# schematic.net
KiCad netlist of a schematic drawn in Altium Designer
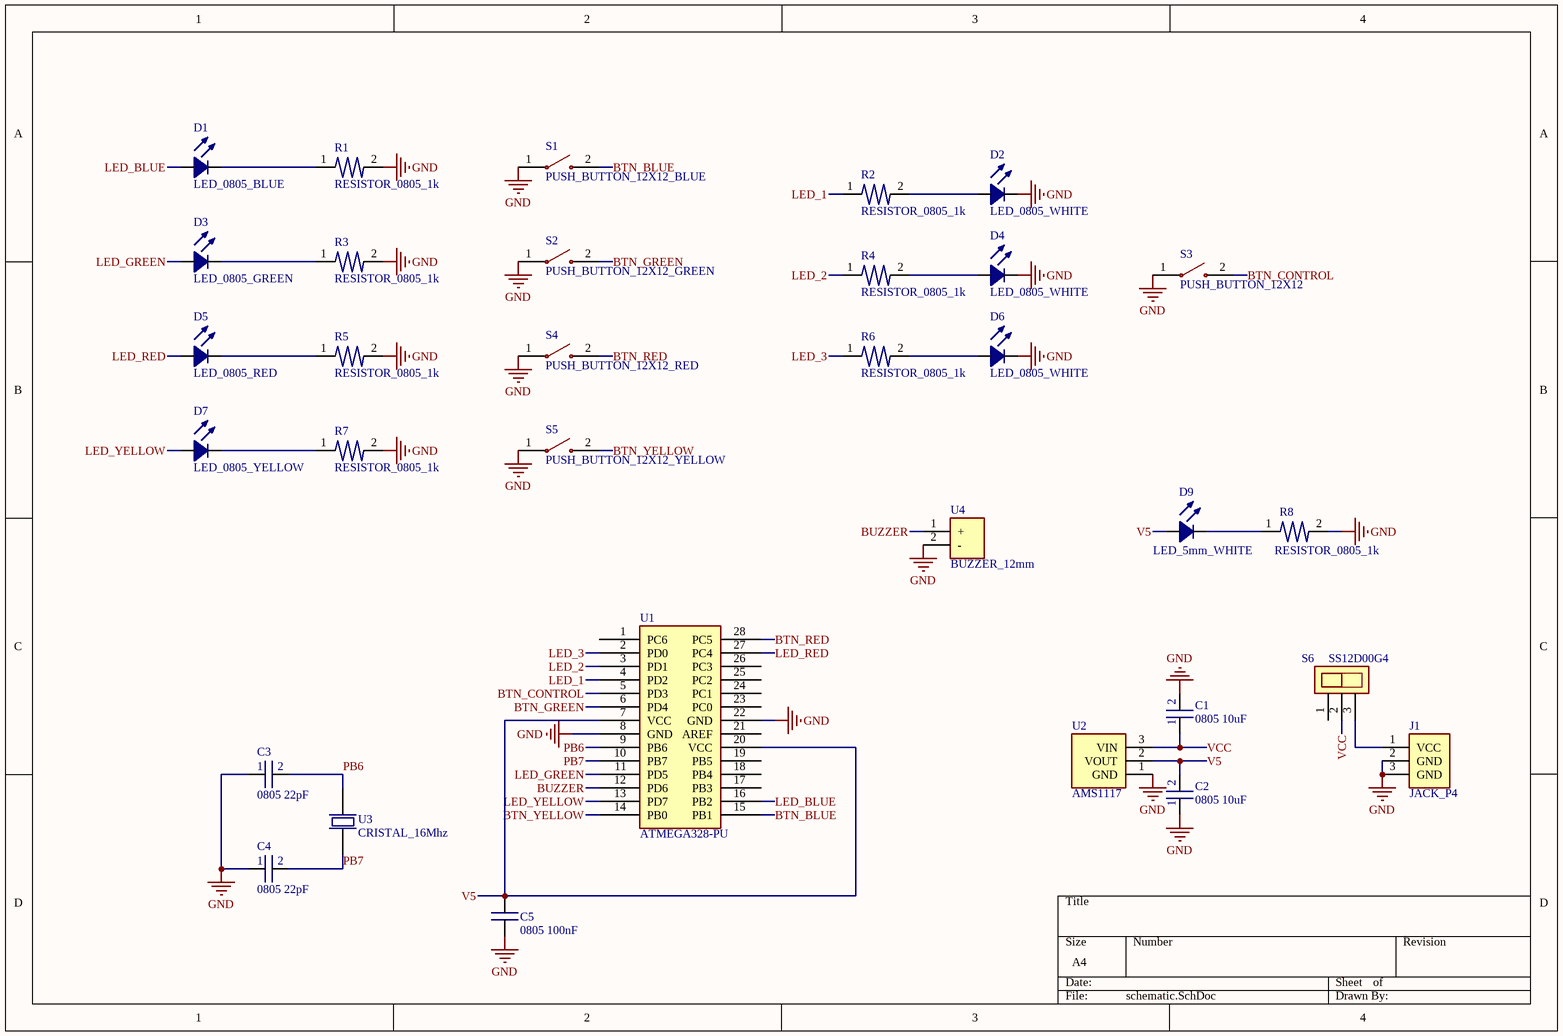
[diagram p0: schematic.SchDoc]

(export (version "E")
  (design (tool "Eeschema 10.0.6"))
  (components
    (comp (ref "C1")
      (value "0805 10uF")
      (footprint "CAPACITOR 0805")
      (libsource (lib "Capacitor Ceramico") (part "CAPACITOR 0805"))
    )
    (comp (ref "C2")
      (value "0805 10uF")
      (footprint "CAPACITOR 0805")
      (libsource (lib "Capacitor Ceramico") (part "CAPACITOR 0805"))
    )
    (comp (ref "C3")
      (value "0805 22pF")
      (footprint "CAPACITOR 0805")
      (libsource (lib "Capacitor Ceramico") (part "CAPACITOR 0805"))
    )
    (comp (ref "C4")
      (value "0805 22pF")
      (footprint "CAPACITOR 0805")
      (libsource (lib "Capacitor Ceramico") (part "CAPACITOR 0805"))
    )
    (comp (ref "C5")
      (value "0805 100nF")
      (footprint "CAPACITOR 0805")
      (libsource (lib "Ceramic Capacitor") (part "CAPACITOR 0805"))
    )
    (comp (ref "D1")
      (value "LED_0805_BLUE")
      (footprint "LED_0805_BLUE")
      (libsource (lib "LED") (part "LED_0805_BLUE"))
    )
    (comp (ref "D2")
      (value "LED_0805_WHITE")
      (footprint "LED_0805_WHITE")
      (libsource (lib "LED") (part "LED_0805_WHITE"))
    )
    (comp (ref "D3")
      (value "LED_0805_GREEN")
      (footprint "LED_0805_GREEN")
      (libsource (lib "LED") (part "LED_0805_GREEN"))
    )
    (comp (ref "D4")
      (value "LED_0805_WHITE")
      (footprint "LED_0805_WHITE")
      (libsource (lib "LED") (part "LED_0805_WHITE"))
    )
    (comp (ref "D5")
      (value "LED_0805_RED")
      (footprint "LED_0805_RED")
      (libsource (lib "LED") (part "LED_0805_RED"))
    )
    (comp (ref "D6")
      (value "LED_0805_WHITE")
      (footprint "LED_0805_WHITE")
      (libsource (lib "LED") (part "LED_0805_WHITE"))
    )
    (comp (ref "D7")
      (value "LED_0805_YELLOW")
      (footprint "LED_0805_YELLOW")
      (libsource (lib "LED") (part "LED_0805_YELLOW"))
    )
    (comp (ref "D9")
      (value "LED_5mm_WHITE")
      (footprint "LED_5mm_WHITE")
      (libsource (lib "LED") (part "LED_5mm_WHITE"))
    )
    (comp (ref "J1") (value "JACK_P4") (footprint "JACK_P4") (libsource (lib "Connectors") (part "JACK_P4")))
    (comp (ref "R1")
      (value "RESISTOR_0805_1k")
      (footprint "RESISTOR_0805_1k")
      (libsource (lib "Resistors") (part "RESISTOR_0805_1k"))
    )
    (comp (ref "R2")
      (value "RESISTOR_0805_1k")
      (footprint "RESISTOR_0805_1k")
      (libsource (lib "Resistors") (part "RESISTOR_0805_1k"))
    )
    (comp (ref "R3")
      (value "RESISTOR_0805_1k")
      (footprint "RESISTOR_0805_1k")
      (libsource (lib "Resistors") (part "RESISTOR_0805_1k"))
    )
    (comp (ref "R4")
      (value "RESISTOR_0805_1k")
      (footprint "RESISTOR_0805_1k")
      (libsource (lib "Resistors") (part "RESISTOR_0805_1k"))
    )
    (comp (ref "R5")
      (value "RESISTOR_0805_1k")
      (footprint "RESISTOR_0805_1k")
      (libsource (lib "Resistors") (part "RESISTOR_0805_1k"))
    )
    (comp (ref "R6")
      (value "RESISTOR_0805_1k")
      (footprint "RESISTOR_0805_1k")
      (libsource (lib "Resistors") (part "RESISTOR_0805_1k"))
    )
    (comp (ref "R7")
      (value "RESISTOR_0805_1k")
      (footprint "RESISTOR_0805_1k")
      (libsource (lib "Resistors") (part "RESISTOR_0805_1k"))
    )
    (comp (ref "R8")
      (value "RESISTOR_0805_1k")
      (footprint "RESISTOR_0805_1k")
      (libsource (lib "Resistors") (part "RESISTOR_0805_1k"))
    )
    (comp (ref "S1")
      (value "PUSH_BUTTON_12X12_BLUE")
      (footprint "PUSH_BUTTON_12X12_BLUE")
      (libsource (lib "Buttons & Switches") (part "PUSH_BUTTON_12X12"))
    )
    (comp (ref "S2")
      (value "PUSH_BUTTON_12X12_GREEN")
      (footprint "PUSH_BUTTON_12X12_GREEN")
      (libsource (lib "Buttons & Switches") (part "PUSH_BUTTON_12X12"))
    )
    (comp (ref "S3")
      (value "PUSH_BUTTON_12X12")
      (footprint "PUSH_BUTTON_12X12_WHITE")
      (libsource (lib "Buttons & Switches") (part "PUSH_BUTTON_12X12"))
    )
    (comp (ref "S4")
      (value "PUSH_BUTTON_12X12_RED")
      (footprint "PUSH_BUTTON_12X12_RED")
      (libsource (lib "Buttons & Switches") (part "PUSH_BUTTON_12X12"))
    )
    (comp (ref "S5")
      (value "PUSH_BUTTON_12X12_YELLOW")
      (footprint "PUSH_BUTTON_12X12_YELLOW")
      (libsource (lib "Buttons & Switches") (part "PUSH_BUTTON_12X12"))
    )
    (comp (ref "S6")
      (value "SS12D00G4")
      (footprint "SS12D00G4")
      (libsource (lib "Buttons & Switches") (part "SS12D00G4"))
    )
    (comp (ref "U1")
      (value "ATMEGA328-PU")
      (footprint "ATMEGA328-PU")
      (description "Microcontroller 8-bit 20MHz  Flash 32KB DIP-28")
      (libsource (lib "Arduino") (part "ATMEGA328-PU"))
    )
    (comp (ref "U2")
      (value "AMS1117")
      (footprint "AMS1117")
      (description "IC REG LINEAR 1A SOT-89-3L")
      (libsource (lib "Voltage Regulators") (part "AMS1117"))
    )
    (comp (ref "U3")
      (value "CRISTAL_16Mhz")
      (footprint "CRISTAL_16Mhz")
      (description "CRYSTAL 16MHZ PTH")
      (libsource (lib "Random") (part "CRISTAL_16Mhz"))
    )
    (comp (ref "U4")
      (value "BUZZER_12mm")
      (footprint "BUZZER_12mm")
      (description "BUZZER MAGNETIC 12MM")
      (libsource (lib "Random") (part "BUZZER_12mm"))
    )
  )
  (nets
    (net (code "2") (name "/BTN_BLUE") (class "Default")
      (node (ref "S1") (pin "2") (pinfunction "2_2") (pintype "passive"))
      (node (ref "U1") (pin "15") (pinfunction "PB1_15") (pintype "passive"))
    )
    (net (code "3") (name "/BTN_CONTROL") (class "Default")
      (node (ref "S3") (pin "2") (pinfunction "2_2") (pintype "passive"))
      (node (ref "U1") (pin "5") (pinfunction "PD3_5") (pintype "passive"))
    )
    (net (code "4") (name "/BTN_GREEN") (class "Default")
      (node (ref "S2") (pin "2") (pinfunction "2_2") (pintype "passive"))
      (node (ref "U1") (pin "6") (pinfunction "PD4_6") (pintype "passive"))
    )
    (net (code "5") (name "/BTN_RED") (class "Default")
      (node (ref "S4") (pin "2") (pinfunction "2_2") (pintype "passive"))
      (node (ref "U1") (pin "28") (pinfunction "PC5_28") (pintype "passive"))
    )
    (net (code "6") (name "/BTN_YELLOW") (class "Default")
      (node (ref "S5") (pin "2") (pinfunction "2_2") (pintype "passive"))
      (node (ref "U1") (pin "14") (pinfunction "PB0_14") (pintype "passive"))
    )
    (net (code "7") (name "/BUZZER") (class "Default")
      (node (ref "U1") (pin "12") (pinfunction "PD6_12") (pintype "passive"))
      (node (ref "U4") (pin "1") (pinfunction "+_1") (pintype "passive"))
    )
    (net (code "8") (name "/LED_1") (class "Default")
      (node (ref "R2") (pin "1") (pinfunction "1_1") (pintype "passive"))
      (node (ref "U1") (pin "4") (pinfunction "PD2_4") (pintype "passive"))
    )
    (net (code "9") (name "/LED_2") (class "Default")
      (node (ref "R4") (pin "1") (pinfunction "1_1") (pintype "passive"))
      (node (ref "U1") (pin "3") (pinfunction "PD1_3") (pintype "passive"))
    )
    (net (code "10") (name "/LED_3") (class "Default")
      (node (ref "R6") (pin "1") (pinfunction "1_1") (pintype "passive"))
      (node (ref "U1") (pin "2") (pinfunction "PD0_2") (pintype "passive"))
    )
    (net (code "11") (name "/LED_BLUE") (class "Default")
      (node (ref "D1") (pin "1") (pinfunction "1_1") (pintype "passive"))
      (node (ref "U1") (pin "16") (pinfunction "PB2_16") (pintype "passive"))
    )
    (net (code "12") (name "/LED_GREEN") (class "Default")
      (node (ref "D3") (pin "1") (pinfunction "1_1") (pintype "passive"))
      (node (ref "U1") (pin "11") (pinfunction "PD5_11") (pintype "passive"))
    )
    (net (code "13") (name "/LED_RED") (class "Default")
      (node (ref "D5") (pin "1") (pinfunction "1_1") (pintype "passive"))
      (node (ref "U1") (pin "27") (pinfunction "PC4_27") (pintype "passive"))
    )
    (net (code "14") (name "/LED_YELLOW") (class "Default")
      (node (ref "D7") (pin "1") (pinfunction "1_1") (pintype "passive"))
      (node (ref "U1") (pin "13") (pinfunction "PD7_13") (pintype "passive"))
    )
    (net (code "15") (name "/PB6") (class "Default")
      (node (ref "C3") (pin "2") (pinfunction "2_2") (pintype "passive"))
      (node (ref "U1") (pin "9") (pinfunction "PB6_9") (pintype "passive"))
      (node (ref "U3") (pin "2") (pinfunction "2_2") (pintype "power_in"))
    )
    (net (code "16") (name "/PB7") (class "Default")
      (node (ref "C4") (pin "2") (pinfunction "2_2") (pintype "passive"))
      (node (ref "U1") (pin "10") (pinfunction "PB7_10") (pintype "passive"))
      (node (ref "U3") (pin "1") (pinfunction "1_1") (pintype "power_in"))
    )
    (net (code "17") (name "/V5") (class "Default")
      (node (ref "C2") (pin "2") (pinfunction "2_2") (pintype "passive"))
      (node (ref "C5") (pin "1") (pinfunction "1_1") (pintype "passive"))
      (node (ref "D9") (pin "1") (pinfunction "1_1") (pintype "passive"))
      (node (ref "U1") (pin "20") (pinfunction "VCC_20") (pintype "passive"))
      (node (ref "U1") (pin "7") (pinfunction "VCC_7") (pintype "passive"))
      (node (ref "U2") (pin "2") (pinfunction "VOUT_2") (pintype "passive"))
    )
    (net (code "18") (name "/VCC") (class "Default")
      (node (ref "C1") (pin "1") (pinfunction "1_1") (pintype "passive"))
      (node (ref "S6") (pin "2") (pintype "passive"))
      (node (ref "U2") (pin "3") (pinfunction "VIN_3") (pintype "passive"))
    )
    (net (code "19") (name "GND") (class "Default")
      (node (ref "C1") (pin "2") (pinfunction "2_2") (pintype "passive"))
      (node (ref "C2") (pin "1") (pinfunction "1_1") (pintype "passive"))
      (node (ref "C3") (pin "1") (pinfunction "1_1") (pintype "passive"))
      (node (ref "C4") (pin "1") (pinfunction "1_1") (pintype "passive"))
      (node (ref "C5") (pin "2") (pinfunction "2_2") (pintype "passive"))
      (node (ref "D2") (pin "2") (pinfunction "2_2") (pintype "passive"))
      (node (ref "D4") (pin "2") (pinfunction "2_2") (pintype "passive"))
      (node (ref "D6") (pin "2") (pinfunction "2_2") (pintype "passive"))
      (node (ref "J1") (pin "2") (pinfunction "GND_2") (pintype "passive"))
      (node (ref "J1") (pin "3") (pinfunction "GND_3") (pintype "passive"))
      (node (ref "R1") (pin "2") (pinfunction "2_2") (pintype "passive"))
      (node (ref "R3") (pin "2") (pinfunction "2_2") (pintype "passive"))
      (node (ref "R5") (pin "2") (pinfunction "2_2") (pintype "passive"))
      (node (ref "R7") (pin "2") (pinfunction "2_2") (pintype "passive"))
      (node (ref "R8") (pin "2") (pinfunction "2_2") (pintype "passive"))
      (node (ref "S1") (pin "1") (pinfunction "1_1") (pintype "passive"))
      (node (ref "S2") (pin "1") (pinfunction "1_1") (pintype "passive"))
      (node (ref "S3") (pin "1") (pinfunction "1_1") (pintype "passive"))
      (node (ref "S4") (pin "1") (pinfunction "1_1") (pintype "passive"))
      (node (ref "S5") (pin "1") (pinfunction "1_1") (pintype "passive"))
      (node (ref "U1") (pin "22") (pinfunction "GND_22") (pintype "passive"))
      (node (ref "U1") (pin "8") (pinfunction "GND_8") (pintype "passive"))
      (node (ref "U2") (pin "1") (pinfunction "GND_1") (pintype "passive"))
      (node (ref "U4") (pin "2") (pinfunction "-_2") (pintype "passive"))
    )
    (net (code "20") (name "Net-(D1-Pad2)") (class "Default")
      (node (ref "D1") (pin "2") (pinfunction "2_2") (pintype "passive"))
      (node (ref "R1") (pin "1") (pinfunction "1_1") (pintype "passive"))
    )
    (net (code "21") (name "Net-(D2-Pad1)") (class "Default")
      (node (ref "D2") (pin "1") (pinfunction "1_1") (pintype "passive"))
      (node (ref "R2") (pin "2") (pinfunction "2_2") (pintype "passive"))
    )
    (net (code "22") (name "Net-(D3-Pad2)") (class "Default")
      (node (ref "D3") (pin "2") (pinfunction "2_2") (pintype "passive"))
      (node (ref "R3") (pin "1") (pinfunction "1_1") (pintype "passive"))
    )
    (net (code "23") (name "Net-(D4-Pad1)") (class "Default")
      (node (ref "D4") (pin "1") (pinfunction "1_1") (pintype "passive"))
      (node (ref "R4") (pin "2") (pinfunction "2_2") (pintype "passive"))
    )
    (net (code "24") (name "Net-(D5-Pad2)") (class "Default")
      (node (ref "D5") (pin "2") (pinfunction "2_2") (pintype "passive"))
      (node (ref "R5") (pin "1") (pinfunction "1_1") (pintype "passive"))
    )
    (net (code "25") (name "Net-(D6-Pad1)") (class "Default")
      (node (ref "D6") (pin "1") (pinfunction "1_1") (pintype "passive"))
      (node (ref "R6") (pin "2") (pinfunction "2_2") (pintype "passive"))
    )
    (net (code "26") (name "Net-(D7-Pad2)") (class "Default")
      (node (ref "D7") (pin "2") (pinfunction "2_2") (pintype "passive"))
      (node (ref "R7") (pin "1") (pinfunction "1_1") (pintype "passive"))
    )
    (net (code "27") (name "Net-(D9-Pad2)") (class "Default")
      (node (ref "D9") (pin "2") (pinfunction "2_2") (pintype "passive"))
      (node (ref "R8") (pin "1") (pinfunction "1_1") (pintype "passive"))
    )
    (net (code "28") (name "Net-(J1-VCC)") (class "Default")
      (node (ref "J1") (pin "1") (pinfunction "VCC_1") (pintype "passive"))
      (node (ref "S6") (pin "3") (pintype "passive"))
    )
    (net (code "29") (name "unconnected-(S6-Pad1)") (class "Default")
      (node (ref "S6") (pin "1") (pintype "passive"))
    )
    (net (code "30") (name "unconnected-(U1-AREF-Pad21)") (class "Default")
      (node (ref "U1") (pin "21") (pinfunction "AREF_21") (pintype "passive"))
    )
    (net (code "31") (name "unconnected-(U1-PB3-Pad17)") (class "Default")
      (node (ref "U1") (pin "17") (pinfunction "PB3_17") (pintype "passive"))
    )
    (net (code "32") (name "unconnected-(U1-PB4-Pad18)") (class "Default")
      (node (ref "U1") (pin "18") (pinfunction "PB4_18") (pintype "passive"))
    )
    (net (code "33") (name "unconnected-(U1-PB5-Pad19)") (class "Default")
      (node (ref "U1") (pin "19") (pinfunction "PB5_19") (pintype "passive"))
    )
    (net (code "34") (name "unconnected-(U1-PC0-Pad23)") (class "Default")
      (node (ref "U1") (pin "23") (pinfunction "PC0_23") (pintype "passive"))
    )
    (net (code "35") (name "unconnected-(U1-PC1-Pad24)") (class "Default")
      (node (ref "U1") (pin "24") (pinfunction "PC1_24") (pintype "passive"))
    )
    (net (code "36") (name "unconnected-(U1-PC2-Pad25)") (class "Default")
      (node (ref "U1") (pin "25") (pinfunction "PC2_25") (pintype "passive"))
    )
    (net (code "37") (name "unconnected-(U1-PC3-Pad26)") (class "Default")
      (node (ref "U1") (pin "26") (pinfunction "PC3_26") (pintype "passive"))
    )
    (net (code "38") (name "unconnected-(U1-PC6-Pad1)") (class "Default")
      (node (ref "U1") (pin "1") (pinfunction "PC6_1") (pintype "passive"))
    )
  )
)
